# CrawlerProc_ver_02.net
KiCad netlist of a schematic drawn in EAGLE
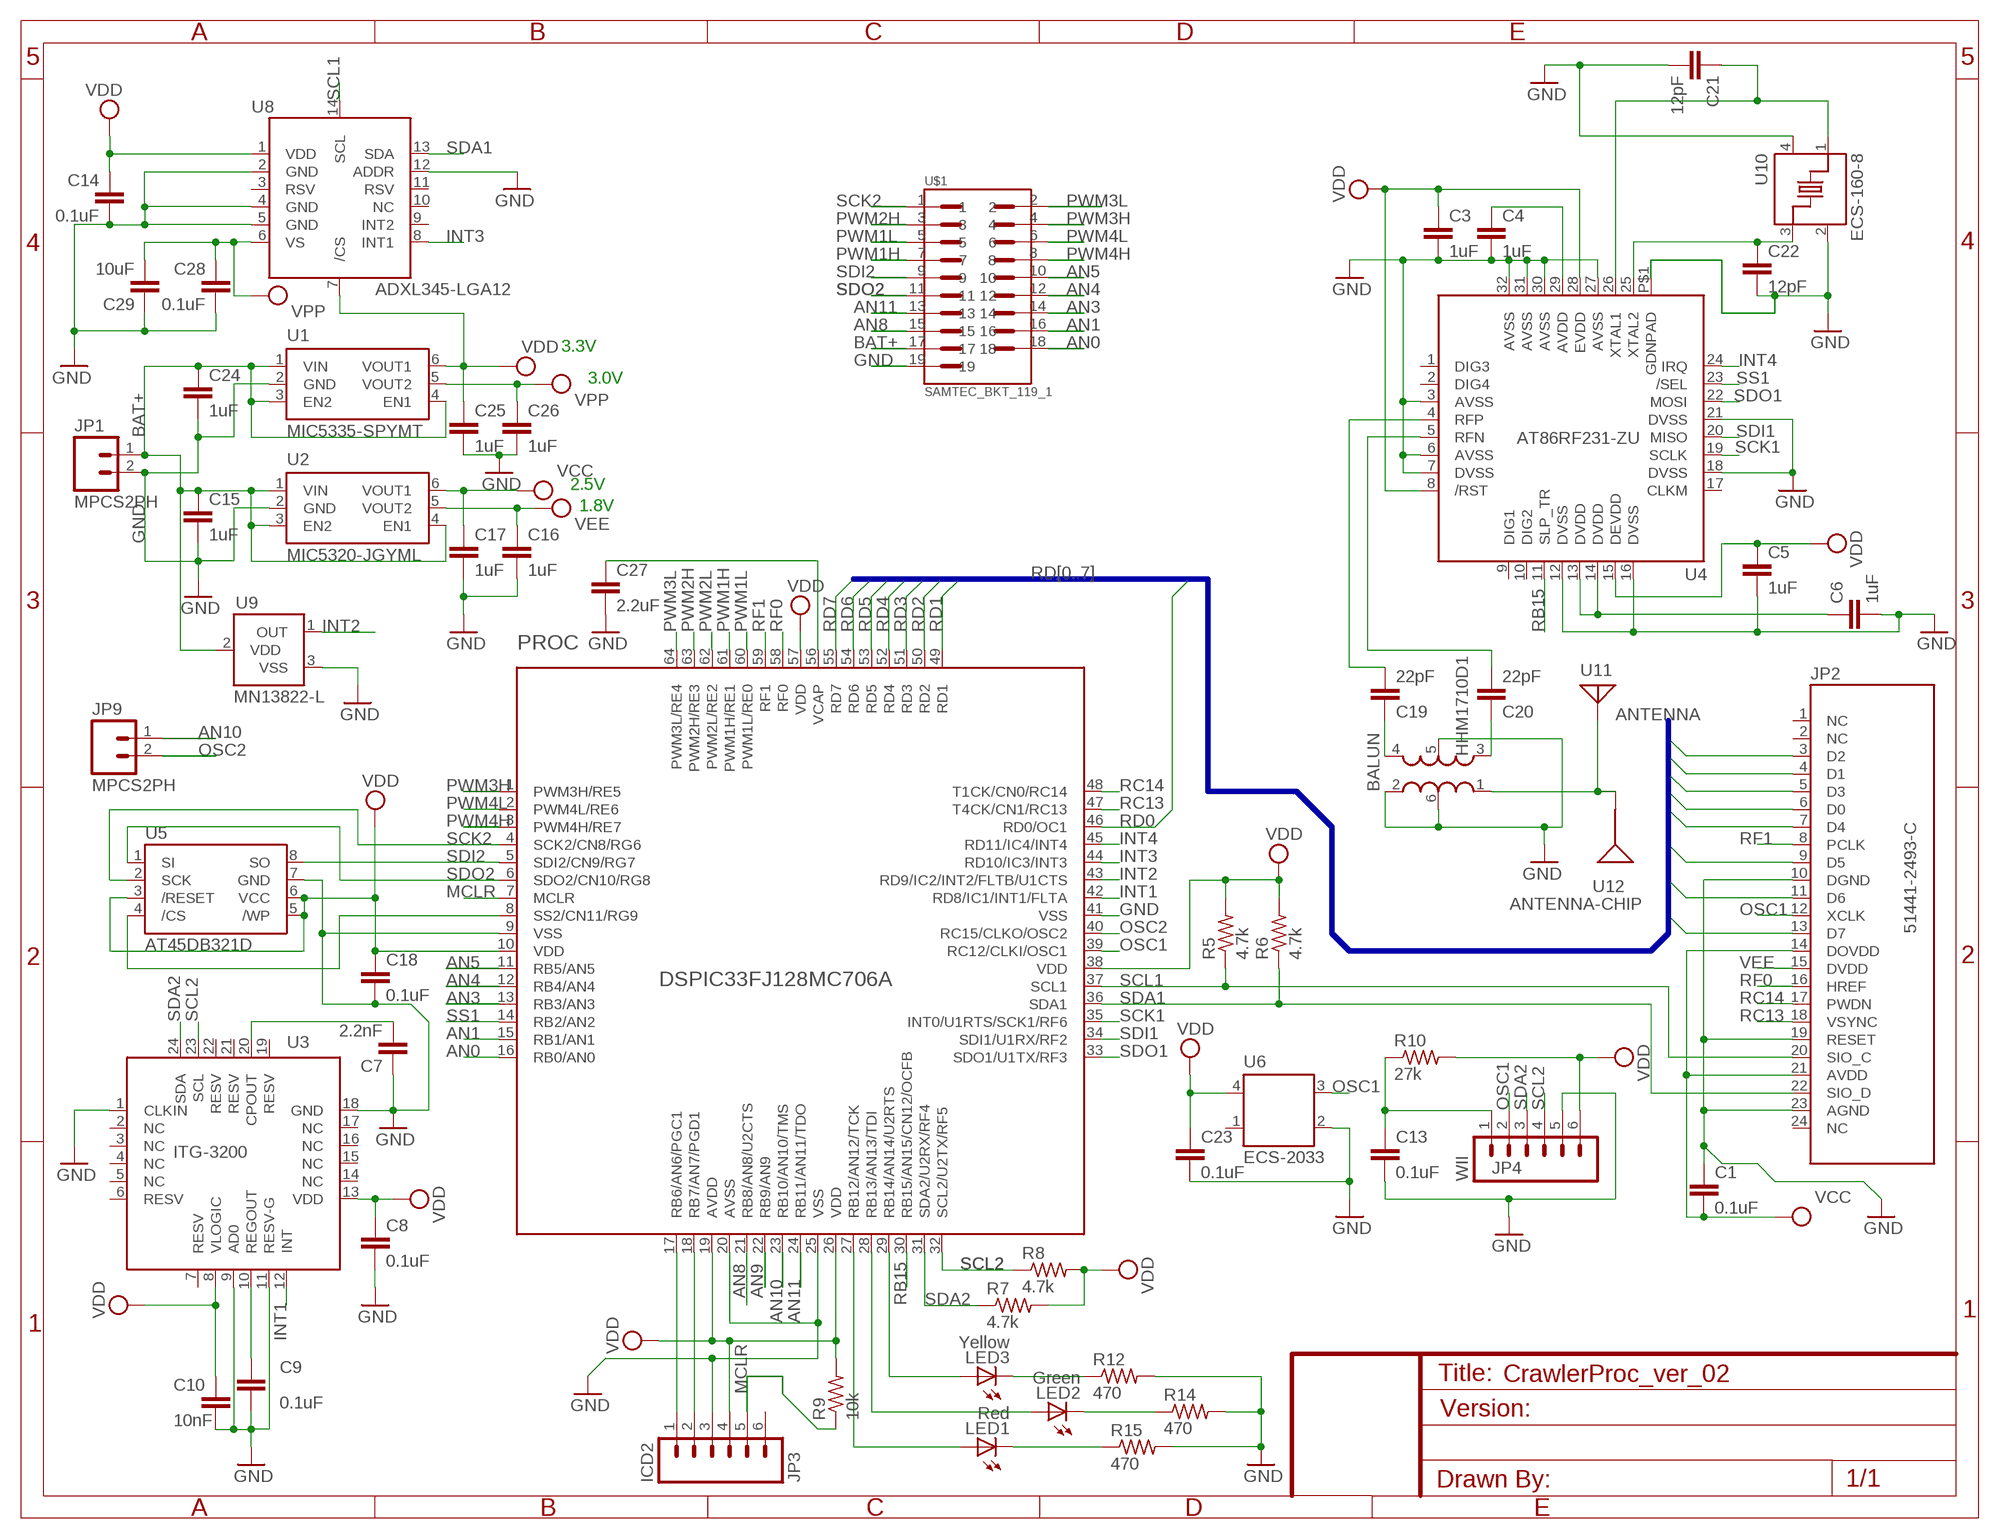
[diagram p0: schematic, sheet 1]

(export (version "E")
  (design (tool "Eeschema 10.0.6"))
  (components
    (comp (ref "BALUN")
      (value "HHM1710D1")
      (footprint "eagle-import:BALUN")
      (libsource (lib "eagle-import") (part "BALUNA"))
    )
    (comp (ref "C1")
      (value "0.1uF")
      (footprint "eagle-import:0402-CAP")
      (libsource (lib "eagle-import") (part "CAP0402-CAP"))
    )
    (comp (ref "C3")
      (value "1uF")
      (footprint "eagle-import:0402-CAP")
      (libsource (lib "eagle-import") (part "CAP0402-CAP"))
    )
    (comp (ref "C4")
      (value "1uF")
      (footprint "eagle-import:0402-CAP")
      (libsource (lib "eagle-import") (part "CAP0402-CAP"))
    )
    (comp (ref "C5")
      (value "1uF")
      (footprint "eagle-import:0402-CAP")
      (libsource (lib "eagle-import") (part "CAP0402-CAP"))
    )
    (comp (ref "C6")
      (value "1uF")
      (footprint "eagle-import:0402-CAP")
      (libsource (lib "eagle-import") (part "CAP0402-CAP"))
    )
    (comp (ref "C7")
      (value "2.2nF")
      (footprint "eagle-import:0402-CAP")
      (libsource (lib "eagle-import") (part "CAP0402-CAP"))
    )
    (comp (ref "C8")
      (value "0.1uF")
      (footprint "eagle-import:0402-CAP")
      (libsource (lib "eagle-import") (part "CAP0402-CAP"))
    )
    (comp (ref "C9")
      (value "0.1uF")
      (footprint "eagle-import:0402-CAP")
      (libsource (lib "eagle-import") (part "CAP0402-CAP"))
    )
    (comp (ref "C10")
      (value "10nF")
      (footprint "eagle-import:0402-CAP")
      (libsource (lib "eagle-import") (part "CAP0402-CAP"))
    )
    (comp (ref "C13")
      (value "0.1uF")
      (footprint "eagle-import:0402-CAP")
      (libsource (lib "eagle-import") (part "CAP0402-CAP"))
    )
    (comp (ref "C14")
      (value "0.1uF")
      (footprint "eagle-import:0402-CAP")
      (libsource (lib "eagle-import") (part "CAP0402-CAP"))
    )
    (comp (ref "C15")
      (value "1uF")
      (footprint "eagle-import:0402-CAP")
      (libsource (lib "eagle-import") (part "CAP0402-CAP"))
    )
    (comp (ref "C16")
      (value "1uF")
      (footprint "eagle-import:0402-CAP")
      (libsource (lib "eagle-import") (part "CAP0402-CAP"))
    )
    (comp (ref "C17")
      (value "1uF")
      (footprint "eagle-import:0402-CAP")
      (libsource (lib "eagle-import") (part "CAP0402-CAP"))
    )
    (comp (ref "C18")
      (value "0.1uF")
      (footprint "eagle-import:0402-CAP")
      (libsource (lib "eagle-import") (part "CAP0402-CAP"))
    )
    (comp (ref "C19")
      (value "22pF")
      (footprint "eagle-import:0402-CAP")
      (libsource (lib "eagle-import") (part "CAP0402-CAP"))
    )
    (comp (ref "C20")
      (value "22pF")
      (footprint "eagle-import:0402-CAP")
      (libsource (lib "eagle-import") (part "CAP0402-CAP"))
    )
    (comp (ref "C21")
      (value "12pF")
      (footprint "eagle-import:0402-CAP")
      (libsource (lib "eagle-import") (part "CAP0402-CAP"))
    )
    (comp (ref "C22")
      (value "12pF")
      (footprint "eagle-import:0402-CAP")
      (libsource (lib "eagle-import") (part "CAP0402-CAP"))
    )
    (comp (ref "C23")
      (value "0.1uF")
      (footprint "eagle-import:0402-CAP")
      (libsource (lib "eagle-import") (part "CAP0402-CAP"))
    )
    (comp (ref "C24")
      (value "1uF")
      (footprint "eagle-import:0402-CAP")
      (libsource (lib "eagle-import") (part "CAP0402-CAP"))
    )
    (comp (ref "C25")
      (value "1uF")
      (footprint "eagle-import:0402-CAP")
      (libsource (lib "eagle-import") (part "CAP0402-CAP"))
    )
    (comp (ref "C26")
      (value "1uF")
      (footprint "eagle-import:0402-CAP")
      (libsource (lib "eagle-import") (part "CAP0402-CAP"))
    )
    (comp (ref "C27")
      (value "2.2uF")
      (footprint "eagle-import:0402-CAP")
      (libsource (lib "eagle-import") (part "CAP0402-CAP"))
    )
    (comp (ref "C28")
      (value "0.1uF")
      (footprint "eagle-import:0402-CAP")
      (libsource (lib "eagle-import") (part "CAP0402-CAP"))
    )
    (comp (ref "C29")
      (value "10uF")
      (footprint "eagle-import:0603-CAP")
      (libsource (lib "eagle-import") (part "CAP0603-CAP"))
    )
    (comp (ref "JP1")
      (value "MPCS2PH")
      (footprint "eagle-import:MOLEX-PICO_CLASP_S2P")
      (libsource (lib "eagle-import") (part "MPCS2PH"))
    )
    (comp (ref "JP2")
      (value "51441-2493-C")
      (footprint "eagle-import:MOLEX-52740-2490")
      (libsource (lib "eagle-import") (part "OV7660FSL_CON-24"))
    )
    (comp (ref "JP3")
      (value "ICD2")
      (footprint "eagle-import:MOLEX-PICO_CLASP_S6P")
      (libsource (lib "eagle-import") (part "MPCS6PH"))
    )
    (comp (ref "JP4")
      (value "WII")
      (footprint "eagle-import:MOLEX-PICO_CLASP_S6P")
      (libsource (lib "eagle-import") (part "MPCS6PH"))
    )
    (comp (ref "JP9")
      (value "MPCS2PH")
      (footprint "eagle-import:MOLEX-PICO_CLASP_S2P")
      (libsource (lib "eagle-import") (part "MPCS2PH"))
    )
    (comp (ref "LED1")
      (value "Red")
      (footprint "eagle-import:CHIP-LED0603")
      (libsource (lib "eagle-import") (part "LEDCHIP-LED0603"))
    )
    (comp (ref "LED2")
      (value "Green")
      (footprint "eagle-import:CHIP-LED0603")
      (libsource (lib "eagle-import") (part "LEDCHIP-LED0603"))
    )
    (comp (ref "LED3")
      (value "Yellow")
      (footprint "eagle-import:CHIP-LED0603")
      (libsource (lib "eagle-import") (part "LEDCHIP-LED0603"))
    )
    (comp (ref "PROC")
      (value "DSPIC33FJ128MC706A")
      (footprint "eagle-import:TQFP64")
      (libsource (lib "eagle-import") (part "DSPIC33FJ128MC706-I/PT"))
    )
    (comp (ref "R5")
      (value "4.7k")
      (footprint "eagle-import:R0402")
      (libsource (lib "eagle-import") (part "R-US_R0402"))
    )
    (comp (ref "R6")
      (value "4.7k")
      (footprint "eagle-import:R0402")
      (libsource (lib "eagle-import") (part "R-US_R0402"))
    )
    (comp (ref "R7")
      (value "4.7k")
      (footprint "eagle-import:R0402")
      (libsource (lib "eagle-import") (part "R-US_R0402"))
    )
    (comp (ref "R8")
      (value "4.7k")
      (footprint "eagle-import:R0402")
      (libsource (lib "eagle-import") (part "R-US_R0402"))
    )
    (comp (ref "R9")
      (value "10k")
      (footprint "eagle-import:R0402")
      (libsource (lib "eagle-import") (part "R-US_R0402"))
    )
    (comp (ref "R10")
      (value "27k")
      (footprint "eagle-import:R0402")
      (libsource (lib "eagle-import") (part "R-US_R0402"))
    )
    (comp (ref "R12")
      (value "470")
      (footprint "eagle-import:R0402")
      (libsource (lib "eagle-import") (part "R-US_R0402"))
    )
    (comp (ref "R14")
      (value "470")
      (footprint "eagle-import:R0402")
      (libsource (lib "eagle-import") (part "R-US_R0402"))
    )
    (comp (ref "R15")
      (value "470")
      (footprint "eagle-import:R0402")
      (libsource (lib "eagle-import") (part "R-US_R0402"))
    )
    (comp (ref "U$1")
      (value "SAMTEC_BKT_119_1")
      (footprint "eagle-import:SAMTEC_19P_1MM_MICRO_CONN")
      (libsource (lib "eagle-import") (part "SAMTEC_BKT_119_1"))
    )
    (comp (ref "U1")
      (value "MIC5335-SPYMT")
      (footprint "eagle-import:MLF-6")
      (libsource (lib "eagle-import") (part "MIC5320-JGYML"))
    )
    (comp (ref "U2")
      (value "MIC5320-JGYML")
      (footprint "eagle-import:MLF-6")
      (libsource (lib "eagle-import") (part "MIC5320-JGYML"))
    )
    (comp (ref "U3")
      (value "ITG-3200")
      (footprint "eagle-import:QFN-24")
      (libsource (lib "eagle-import") (part "ITG-3200-00"))
    )
    (comp (ref "U4")
      (value "AT86RF231-ZU")
      (footprint "eagle-import:QFN-32")
      (libsource (lib "eagle-import") (part "AT86RF231-ZU"))
    )
    (comp (ref "U5")
      (value "AT45DB321D")
      (footprint "eagle-import:MLF(VDFN)-8")
      (libsource (lib "eagle-import") (part "AT45DB321D"))
    )
    (comp (ref "U6")
      (value "ECS-2033")
      (footprint "eagle-import:OSCILLATOR-SMD")
      (libsource (lib "eagle-import") (part "OSCILLATORS"))
    )
    (comp (ref "U8")
      (value "ADXL345-LGA12")
      (footprint "eagle-import:LGA14")
      (libsource (lib "eagle-import") (part "ADXL345"))
    )
    (comp (ref "U9")
      (value "MN13822-L")
      (footprint "eagle-import:SOT-23-3")
      (libsource (lib "eagle-import") (part "VOL_DETECTOR"))
    )
    (comp (ref "U10")
      (value "ECS-160-8")
      (footprint "eagle-import:CRYSTAL-SMD")
      (libsource (lib "eagle-import") (part "CRYSTALS"))
    )
    (comp (ref "U11")
      (value "ANTENNA")
      (footprint "eagle-import:ANTENNA_PAD")
      (libsource (lib "eagle-import") (part "ANTENNA"))
    )
    (comp (ref "U12")
      (value "ANTENNA-CHIP")
      (footprint "eagle-import:ANTENNA-CHIP")
      (libsource (lib "eagle-import") (part "ANTENNA-CHIP"))
    )
  )
  (nets
    (net (code "1") (name "/AN0") (class "Default")
      (node (ref "PROC") (pin "16") (pinfunction "RB0/AN0_16") (pintype "bidirectional"))
      (node (ref "U$1") (pin "18") (pinfunction "18_18") (pintype "passive"))
    )
    (net (code "2") (name "/AN1") (class "Default")
      (node (ref "PROC") (pin "15") (pinfunction "RB1/AN1_15") (pintype "bidirectional"))
      (node (ref "U$1") (pin "16") (pinfunction "16_16") (pintype "passive"))
    )
    (net (code "3") (name "/AN3") (class "Default")
      (node (ref "PROC") (pin "13") (pinfunction "RB3/AN3_13") (pintype "bidirectional"))
      (node (ref "U$1") (pin "14") (pinfunction "14_14") (pintype "passive"))
    )
    (net (code "4") (name "/AN4") (class "Default")
      (node (ref "PROC") (pin "12") (pinfunction "RB4/AN4_12") (pintype "bidirectional"))
      (node (ref "U$1") (pin "12") (pinfunction "12_12") (pintype "passive"))
    )
    (net (code "5") (name "/AN5") (class "Default")
      (node (ref "PROC") (pin "11") (pinfunction "RB5/AN5_11") (pintype "bidirectional"))
      (node (ref "U$1") (pin "10") (pinfunction "10_10") (pintype "passive"))
    )
    (net (code "6") (name "/AN8") (class "Default")
      (node (ref "PROC") (pin "21") (pinfunction "RB8/AN8/U2CTS_21") (pintype "bidirectional"))
      (node (ref "U$1") (pin "15") (pinfunction "15_15") (pintype "passive"))
    )
    (net (code "7") (name "/AN9") (class "Default")
      (node (ref "PROC") (pin "22") (pinfunction "RB9/AN9_22") (pintype "bidirectional"))
    )
    (net (code "8") (name "/AN10") (class "Default")
      (node (ref "JP9") (pin "1") (pinfunction "1_1") (pintype "passive"))
      (node (ref "PROC") (pin "23") (pinfunction "RB10/AN10/TMS_23") (pintype "bidirectional"))
    )
    (net (code "9") (name "/AN11") (class "Default")
      (node (ref "PROC") (pin "24") (pinfunction "RB11/AN11/TDO_24") (pintype "bidirectional"))
      (node (ref "U$1") (pin "13") (pinfunction "13_13") (pintype "passive"))
    )
    (net (code "10") (name "/BAT+") (class "Default")
      (node (ref "C15") (pin "1") (pinfunction "1_1") (pintype "passive"))
      (node (ref "C24") (pin "1") (pinfunction "1_1") (pintype "passive"))
      (node (ref "JP1") (pin "1") (pinfunction "1_1") (pintype "passive"))
      (node (ref "U$1") (pin "17") (pinfunction "17_17") (pintype "passive"))
      (node (ref "U1") (pin "1") (pinfunction "VIN_1") (pintype "bidirectional"))
      (node (ref "U1") (pin "3") (pinfunction "EN2_3") (pintype "bidirectional"))
      (node (ref "U1") (pin "4") (pinfunction "EN1_4") (pintype "bidirectional"))
      (node (ref "U2") (pin "1") (pinfunction "VIN_1") (pintype "bidirectional"))
      (node (ref "U2") (pin "3") (pinfunction "EN2_3") (pintype "bidirectional"))
      (node (ref "U2") (pin "4") (pinfunction "EN1_4") (pintype "bidirectional"))
      (node (ref "U9") (pin "2") (pinfunction "VDD_2") (pintype "bidirectional"))
    )
    (net (code "11") (name "/INT1") (class "Default")
      (node (ref "PROC") (pin "42") (pinfunction "RD8/IC1/INT1/FLTA_42") (pintype "bidirectional"))
      (node (ref "U3") (pin "12") (pinfunction "INT_12") (pintype "bidirectional"))
    )
    (net (code "12") (name "/INT2") (class "Default")
      (node (ref "PROC") (pin "43") (pinfunction "RD9/IC2/INT2/FLTB/U1CTS_43") (pintype "bidirectional"))
      (node (ref "U9") (pin "1") (pinfunction "OUT_1") (pintype "bidirectional"))
    )
    (net (code "13") (name "/INT3") (class "Default")
      (node (ref "PROC") (pin "44") (pinfunction "RD10/IC3/INT3_44") (pintype "bidirectional"))
      (node (ref "U8") (pin "8") (pinfunction "INT1_8") (pintype "bidirectional"))
    )
    (net (code "14") (name "/INT4") (class "Default")
      (node (ref "PROC") (pin "45") (pinfunction "RD11/IC4/INT4_45") (pintype "bidirectional"))
      (node (ref "U4") (pin "24") (pinfunction "IRQ_24") (pintype "bidirectional"))
    )
    (net (code "15") (name "/MCLR") (class "Default")
      (node (ref "JP3") (pin "5") (pinfunction "5_5") (pintype "passive"))
      (node (ref "PROC") (pin "7") (pinfunction "MCLR_7") (pintype "input"))
      (node (ref "R9") (pin "1") (pinfunction "1_1") (pintype "passive"))
    )
    (net (code "16") (name "/OSC1") (class "Default")
      (node (ref "JP2") (pin "12") (pinfunction "XCLK_12") (pintype "bidirectional"))
      (node (ref "JP4") (pin "2") (pinfunction "2_2") (pintype "passive"))
      (node (ref "PROC") (pin "39") (pinfunction "RC12/CLKI/OSC1_39") (pintype "bidirectional"))
      (node (ref "U6") (pin "3") (pinfunction "OUT_3") (pintype "bidirectional"))
    )
    (net (code "17") (name "/OSC2") (class "Default")
      (node (ref "JP9") (pin "2") (pinfunction "2_2") (pintype "passive"))
      (node (ref "PROC") (pin "40") (pinfunction "RC15/CLKO/OSC2_40") (pintype "bidirectional"))
    )
    (net (code "18") (name "/PWM1H") (class "Default")
      (node (ref "PROC") (pin "61") (pinfunction "PWM1H/RE1_61") (pintype "bidirectional"))
      (node (ref "U$1") (pin "7") (pinfunction "7_7") (pintype "passive"))
    )
    (net (code "19") (name "/PWM1L") (class "Default")
      (node (ref "PROC") (pin "60") (pinfunction "PWM1L/RE0_60") (pintype "bidirectional"))
      (node (ref "U$1") (pin "5") (pinfunction "5_5") (pintype "passive"))
    )
    (net (code "20") (name "/PWM2H") (class "Default")
      (node (ref "PROC") (pin "63") (pinfunction "PWM2H/RE3_63") (pintype "bidirectional"))
      (node (ref "U$1") (pin "3") (pinfunction "3_3") (pintype "passive"))
    )
    (net (code "21") (name "/PWM2L") (class "Default")
      (node (ref "PROC") (pin "62") (pinfunction "PWM2L/RE2_62") (pintype "bidirectional"))
    )
    (net (code "22") (name "/PWM3H") (class "Default")
      (node (ref "PROC") (pin "1") (pinfunction "PWM3H/RE5_1") (pintype "bidirectional"))
      (node (ref "U$1") (pin "4") (pinfunction "4_4") (pintype "passive"))
    )
    (net (code "23") (name "/PWM3L") (class "Default")
      (node (ref "PROC") (pin "64") (pinfunction "PWM3L/RE4_64") (pintype "bidirectional"))
      (node (ref "U$1") (pin "2") (pinfunction "2_2") (pintype "passive"))
    )
    (net (code "24") (name "/PWM4H") (class "Default")
      (node (ref "PROC") (pin "3") (pinfunction "PWM4H/RE7_3") (pintype "bidirectional"))
      (node (ref "U$1") (pin "8") (pinfunction "8_8") (pintype "passive"))
    )
    (net (code "25") (name "/PWM4L") (class "Default")
      (node (ref "PROC") (pin "2") (pinfunction "PWM4L/RE6_2") (pintype "bidirectional"))
      (node (ref "U$1") (pin "6") (pinfunction "6_6") (pintype "passive"))
    )
    (net (code "26") (name "/RB15") (class "Default")
      (node (ref "PROC") (pin "30") (pinfunction "RB15/AN15/CN12/OCFB_30") (pintype "bidirectional"))
      (node (ref "U4") (pin "11") (pinfunction "SLP_TR_11") (pintype "bidirectional"))
    )
    (net (code "27") (name "/RC13") (class "Default")
      (node (ref "JP2") (pin "18") (pinfunction "VSYNC_18") (pintype "bidirectional"))
      (node (ref "PROC") (pin "47") (pinfunction "T4CK/CN1/RC13_47") (pintype "bidirectional"))
    )
    (net (code "28") (name "/RC14") (class "Default")
      (node (ref "JP2") (pin "17") (pinfunction "PWDN_17") (pintype "bidirectional"))
      (node (ref "PROC") (pin "48") (pinfunction "T1CK/CN0/RC14_48") (pintype "bidirectional"))
    )
    (net (code "29") (name "/RD0") (class "Default")
      (node (ref "JP2") (pin "6") (pinfunction "D0_6") (pintype "bidirectional"))
      (node (ref "PROC") (pin "46") (pinfunction "RD0/OC1_46") (pintype "bidirectional"))
    )
    (net (code "30") (name "/RD1") (class "Default")
      (node (ref "JP2") (pin "4") (pinfunction "D1_4") (pintype "bidirectional"))
      (node (ref "PROC") (pin "49") (pinfunction "RD1_49") (pintype "bidirectional"))
    )
    (net (code "31") (name "/RD2") (class "Default")
      (node (ref "JP2") (pin "3") (pinfunction "D2_3") (pintype "bidirectional"))
      (node (ref "PROC") (pin "50") (pinfunction "RD2_50") (pintype "bidirectional"))
    )
    (net (code "32") (name "/RD3") (class "Default")
      (node (ref "JP2") (pin "5") (pinfunction "D3_5") (pintype "bidirectional"))
      (node (ref "PROC") (pin "51") (pinfunction "RD3_51") (pintype "bidirectional"))
    )
    (net (code "33") (name "/RD4") (class "Default")
      (node (ref "JP2") (pin "7") (pinfunction "D4_7") (pintype "bidirectional"))
      (node (ref "PROC") (pin "52") (pinfunction "RD4_52") (pintype "bidirectional"))
    )
    (net (code "34") (name "/RD5") (class "Default")
      (node (ref "JP2") (pin "9") (pinfunction "D5_9") (pintype "bidirectional"))
      (node (ref "PROC") (pin "53") (pinfunction "RD5_53") (pintype "bidirectional"))
    )
    (net (code "35") (name "/RD6") (class "Default")
      (node (ref "JP2") (pin "11") (pinfunction "D6_11") (pintype "bidirectional"))
      (node (ref "PROC") (pin "54") (pinfunction "RD6_54") (pintype "bidirectional"))
    )
    (net (code "36") (name "/RD7") (class "Default")
      (node (ref "JP2") (pin "13") (pinfunction "D7_13") (pintype "bidirectional"))
      (node (ref "PROC") (pin "55") (pinfunction "RD7_55") (pintype "bidirectional"))
    )
    (net (code "38") (name "/RF0") (class "Default")
      (node (ref "JP2") (pin "16") (pinfunction "HREF_16") (pintype "bidirectional"))
      (node (ref "PROC") (pin "58") (pinfunction "RF0_58") (pintype "bidirectional"))
    )
    (net (code "39") (name "/RF1") (class "Default")
      (node (ref "JP2") (pin "8") (pinfunction "PCLK_8") (pintype "bidirectional"))
      (node (ref "PROC") (pin "59") (pinfunction "RF1_59") (pintype "bidirectional"))
    )
    (net (code "40") (name "/SCK1") (class "Default")
      (node (ref "PROC") (pin "35") (pinfunction "INT0/U1RTS/SCK1/RF6_35") (pintype "bidirectional"))
      (node (ref "U4") (pin "19") (pinfunction "SCLK_19") (pintype "bidirectional"))
    )
    (net (code "41") (name "/SCK2") (class "Default")
      (node (ref "PROC") (pin "4") (pinfunction "SCK2/CN8/RG6_4") (pintype "bidirectional"))
      (node (ref "U$1") (pin "1") (pinfunction "1_1") (pintype "passive"))
      (node (ref "U5") (pin "2") (pinfunction "SCK_2") (pintype "bidirectional"))
    )
    (net (code "42") (name "/SCL1") (class "Default")
      (node (ref "JP2") (pin "20") (pinfunction "SIO_C_20") (pintype "bidirectional"))
      (node (ref "PROC") (pin "37") (pinfunction "SCL1_37") (pintype "bidirectional"))
      (node (ref "R5") (pin "1") (pinfunction "1_1") (pintype "passive"))
      (node (ref "U8") (pin "14") (pinfunction "SCL_14") (pintype "bidirectional"))
    )
    (net (code "43") (name "/SCL2") (class "Default")
      (node (ref "JP4") (pin "4") (pinfunction "4_4") (pintype "passive"))
      (node (ref "PROC") (pin "32") (pinfunction "SCL2/U2TX/RF5_32") (pintype "bidirectional"))
      (node (ref "R8") (pin "1") (pinfunction "1_1") (pintype "passive"))
      (node (ref "U3") (pin "23") (pinfunction "SCL_23") (pintype "bidirectional"))
    )
    (net (code "44") (name "/SDA1") (class "Default")
      (node (ref "JP2") (pin "22") (pinfunction "SIO_D_22") (pintype "bidirectional"))
      (node (ref "PROC") (pin "36") (pinfunction "SDA1_36") (pintype "bidirectional"))
      (node (ref "R6") (pin "1") (pinfunction "1_1") (pintype "passive"))
      (node (ref "U8") (pin "13") (pinfunction "SDA_13") (pintype "bidirectional"))
    )
    (net (code "45") (name "/SDA2") (class "Default")
      (node (ref "JP4") (pin "3") (pinfunction "3_3") (pintype "passive"))
      (node (ref "PROC") (pin "31") (pinfunction "SDA2/U2RX/RF4_31") (pintype "bidirectional"))
      (node (ref "R7") (pin "1") (pinfunction "1_1") (pintype "passive"))
      (node (ref "U3") (pin "24") (pinfunction "SDA_24") (pintype "bidirectional"))
    )
    (net (code "46") (name "/SDI1") (class "Default")
      (node (ref "PROC") (pin "34") (pinfunction "SDI1/U1RX/RF2_34") (pintype "bidirectional"))
      (node (ref "U4") (pin "20") (pinfunction "MISO_20") (pintype "bidirectional"))
    )
    (net (code "47") (name "/SDI2") (class "Default")
      (node (ref "PROC") (pin "5") (pinfunction "SDI2/CN9/RG7_5") (pintype "bidirectional"))
      (node (ref "U$1") (pin "9") (pinfunction "9_9") (pintype "passive"))
      (node (ref "U5") (pin "8") (pinfunction "SO_8") (pintype "bidirectional"))
    )
    (net (code "48") (name "/SDO1") (class "Default")
      (node (ref "PROC") (pin "33") (pinfunction "SDO1/U1TX/RF3_33") (pintype "bidirectional"))
      (node (ref "U4") (pin "22") (pinfunction "MOSI_22") (pintype "bidirectional"))
    )
    (net (code "49") (name "/SDO2") (class "Default")
      (node (ref "PROC") (pin "6") (pinfunction "SDO2/CN10/RG8_6") (pintype "bidirectional"))
      (node (ref "U$1") (pin "11") (pinfunction "11_11") (pintype "passive"))
      (node (ref "U5") (pin "1") (pinfunction "SI_1") (pintype "bidirectional"))
    )
    (net (code "50") (name "/SS1") (class "Default")
      (node (ref "PROC") (pin "14") (pinfunction "RB2/AN2_14") (pintype "bidirectional"))
      (node (ref "U4") (pin "23") (pinfunction "/SEL_23") (pintype "bidirectional"))
    )
    (net (code "51") (name "GND") (class "Default")
      (node (ref "BALUN") (pin "2") (pinfunction "RFGND_2") (pintype "bidirectional"))
      (node (ref "BALUN") (pin "5") (pinfunction "GND_5") (pintype "bidirectional"))
      (node (ref "BALUN") (pin "6") (pinfunction "NC_6") (pintype "bidirectional"))
      (node (ref "C1") (pin "1") (pinfunction "1_1") (pintype "passive"))
      (node (ref "C10") (pin "2") (pinfunction "2_2") (pintype "passive"))
      (node (ref "C13") (pin "2") (pinfunction "2_2") (pintype "passive"))
      (node (ref "C14") (pin "2") (pinfunction "2_2") (pintype "passive"))
      (node (ref "C15") (pin "2") (pinfunction "2_2") (pintype "passive"))
      (node (ref "C16") (pin "2") (pinfunction "2_2") (pintype "passive"))
      (node (ref "C17") (pin "2") (pinfunction "2_2") (pintype "passive"))
      (node (ref "C18") (pin "2") (pinfunction "2_2") (pintype "passive"))
      (node (ref "C21") (pin "2") (pinfunction "2_2") (pintype "passive"))
      (node (ref "C22") (pin "2") (pinfunction "2_2") (pintype "passive"))
      (node (ref "C23") (pin "2") (pinfunction "2_2") (pintype "passive"))
      (node (ref "C24") (pin "2") (pinfunction "2_2") (pintype "passive"))
      (node (ref "C25") (pin "2") (pinfunction "2_2") (pintype "passive"))
      (node (ref "C26") (pin "2") (pinfunction "2_2") (pintype "passive"))
      (node (ref "C27") (pin "2") (pinfunction "2_2") (pintype "passive"))
      (node (ref "C28") (pin "2") (pinfunction "2_2") (pintype "passive"))
      (node (ref "C29") (pin "1") (pinfunction "1_1") (pintype "passive"))
      (node (ref "C3") (pin "2") (pinfunction "2_2") (pintype "passive"))
      (node (ref "C4") (pin "2") (pinfunction "2_2") (pintype "passive"))
      (node (ref "C5") (pin "2") (pinfunction "2_2") (pintype "passive"))
      (node (ref "C6") (pin "2") (pinfunction "2_2") (pintype "passive"))
      (node (ref "C7") (pin "1") (pinfunction "1_1") (pintype "passive"))
      (node (ref "C8") (pin "2") (pinfunction "2_2") (pintype "passive"))
      (node (ref "C9") (pin "2") (pinfunction "2_2") (pintype "passive"))
      (node (ref "JP1") (pin "2") (pinfunction "2_2") (pintype "passive"))
      (node (ref "JP2") (pin "10") (pinfunction "DGND_10") (pintype "bidirectional"))
      (node (ref "JP2") (pin "19") (pinfunction "RESET_19") (pintype "bidirectional"))
      (node (ref "JP2") (pin "23") (pinfunction "AGND_23") (pintype "bidirectional"))
      (node (ref "JP3") (pin "3") (pinfunction "3_3") (pintype "passive"))
      (node (ref "JP4") (pin "5") (pinfunction "5_5") (pintype "passive"))
      (node (ref "PROC") (pin "20") (pinfunction "AVSS_20") (pintype "power_in"))
      (node (ref "PROC") (pin "25") (pinfunction "VSS_25") (pintype "power_in"))
      (node (ref "PROC") (pin "41") (pinfunction "VSS_41") (pintype "power_in"))
      (node (ref "PROC") (pin "9") (pinfunction "VSS_9") (pintype "power_in"))
      (node (ref "R12") (pin "2") (pinfunction "2_2") (pintype "passive"))
      (node (ref "R14") (pin "2") (pinfunction "2_2") (pintype "passive"))
      (node (ref "R15") (pin "2") (pinfunction "2_2") (pintype "passive"))
      (node (ref "U$1") (pin "19") (pinfunction "19_19") (pintype "passive"))
      (node (ref "U1") (pin "2") (pinfunction "GND_2") (pintype "bidirectional"))
      (node (ref "U10") (pin "2") (pinfunction "GND_2") (pintype "bidirectional"))
      (node (ref "U10") (pin "4") (pinfunction "GND_4") (pintype "bidirectional"))
      (node (ref "U2") (pin "2") (pinfunction "GND_2") (pintype "bidirectional"))
      (node (ref "U3") (pin "1") (pinfunction "CLKIN_1") (pintype "bidirectional"))
      (node (ref "U3") (pin "11") (pinfunction "RESV-G_11") (pintype "bidirectional"))
      (node (ref "U3") (pin "18") (pinfunction "GND_18") (pintype "bidirectional"))
      (node (ref "U3") (pin "9") (pinfunction "AD0_9") (pintype "bidirectional"))
      (node (ref "U4") (pin "12") (pinfunction "DVSS_12") (pintype "bidirectional"))
      (node (ref "U4") (pin "16") (pinfunction "DVSS_16") (pintype "bidirectional"))
      (node (ref "U4") (pin "18") (pinfunction "DVSS_18") (pintype "bidirectional"))
      (node (ref "U4") (pin "21") (pinfunction "DVSS_21") (pintype "bidirectional"))
      (node (ref "U4") (pin "27") (pinfunction "AVSS_27") (pintype "bidirectional"))
      (node (ref "U4") (pin "3") (pinfunction "AVSS_3") (pintype "bidirectional"))
      (node (ref "U4") (pin "30") (pinfunction "AVSS_30") (pintype "bidirectional"))
      (node (ref "U4") (pin "31") (pinfunction "AVSS_31") (pintype "bidirectional"))
      (node (ref "U4") (pin "32") (pinfunction "AVSS_32") (pintype "bidirectional"))
      (node (ref "U4") (pin "6") (pinfunction "AVSS_6") (pintype "bidirectional"))
      (node (ref "U4") (pin "7") (pinfunction "DVSS_7") (pintype "bidirectional"))
      (node (ref "U4") (pin "P$1") (pinfunction "GDNPAD_P$1") (pintype "bidirectional"))
      (node (ref "U5") (pin "7") (pinfunction "GND_7") (pintype "bidirectional"))
      (node (ref "U6") (pin "2") (pinfunction "GND_2") (pintype "bidirectional"))
      (node (ref "U8") (pin "12") (pinfunction "ADDR_12") (pintype "bidirectional"))
      (node (ref "U8") (pin "2") (pinfunction "GND_2") (pintype "bidirectional"))
      (node (ref "U8") (pin "4") (pinfunction "GND_4") (pintype "bidirectional"))
      (node (ref "U8") (pin "5") (pinfunction "GND_5") (pintype "bidirectional"))
      (node (ref "U9") (pin "3") (pinfunction "VSS_3") (pintype "bidirectional"))
    )
    (net (code "52") (name "Net-(BALUN-BAL3)") (class "Default")
      (node (ref "BALUN") (pin "3") (pinfunction "BAL3_3") (pintype "bidirectional"))
      (node (ref "C20") (pin "1") (pinfunction "1_1") (pintype "passive"))
    )
    (net (code "53") (name "Net-(BALUN-BAL4)") (class "Default")
      (node (ref "BALUN") (pin "4") (pinfunction "BAL4_4") (pintype "bidirectional"))
      (node (ref "C19") (pin "1") (pinfunction "1_1") (pintype "passive"))
    )
    (net (code "54") (name "Net-(BALUN-UNBAL)") (class "Default")
      (node (ref "BALUN") (pin "1") (pinfunction "UNBAL_1") (pintype "bidirectional"))
      (node (ref "U11") (pin "P$1") (pinfunction "1_P$1") (pintype "output"))
      (node (ref "U12") (pin "SIG") (pinfunction "SIGNAL_SIG") (pintype "bidirectional"))
    )
    (net (code "55") (name "Net-(C6-Pad1)") (class "Default")
      (node (ref "C6") (pin "1") (pinfunction "1_1") (pintype "passive"))
      (node (ref "U4") (pin "13") (pinfunction "DVDD_13") (pintype "bidirectional"))
      (node (ref "U4") (pin "14") (pinfunction "DVDD_14") (pintype "bidirectional"))
    )
    (net (code "56") (name "Net-(C13-Pad1)") (class "Default")
      (node (ref "C13") (pin "1") (pinfunction "1_1") (pintype "passive"))
      (node (ref "JP4") (pin "1") (pinfunction "1_1") (pintype "passive"))
      (node (ref "R10") (pin "1") (pinfunction "1_1") (pintype "passive"))
    )
    (net (code "57") (name "Net-(LED1-PadC)") (class "Default")
      (node (ref "LED1") (pin "C") (pinfunction "C_C") (pintype "passive"))
      (node (ref "R15") (pin "1") (pinfunction "1_1") (pintype "passive"))
    )
    (net (code "58") (name "Net-(LED2-PadC)") (class "Default")
      (node (ref "LED2") (pin "C") (pinfunction "C_C") (pintype "passive"))
      (node (ref "R14") (pin "1") (pinfunction "1_1") (pintype "passive"))
    )
    (net (code "59") (name "Net-(LED3-PadC)") (class "Default")
      (node (ref "LED3") (pin "C") (pinfunction "C_C") (pintype "passive"))
      (node (ref "R12") (pin "1") (pinfunction "1_1") (pintype "passive"))
    )
    (net (code "60") (name "Net-(PROC-RB6{slash}AN6{slash}PGC1)") (class "Default")
      (node (ref "JP3") (pin "1") (pinfunction "1_1") (pintype "passive"))
      (node (ref "PROC") (pin "17") (pinfunction "RB6/AN6/PGC1_17") (pintype "bidirectional"))
    )
    (net (code "61") (name "Net-(PROC-RB7{slash}AN7{slash}PGD1)") (class "Default")
      (node (ref "JP3") (pin "2") (pinfunction "2_2") (pintype "passive"))
      (node (ref "PROC") (pin "18") (pinfunction "RB7/AN7/PGD1_18") (pintype "bidirectional"))
    )
    (net (code "62") (name "Net-(PROC-RB12{slash}AN12{slash}TCK)") (class "Default")
      (node (ref "LED1") (pin "A") (pinfunction "A_A") (pintype "passive"))
      (node (ref "PROC") (pin "27") (pinfunction "RB12/AN12/TCK_27") (pintype "bidirectional"))
    )
    (net (code "63") (name "Net-(PROC-RB13{slash}AN13{slash}TDI)") (class "Default")
      (node (ref "LED2") (pin "A") (pinfunction "A_A") (pintype "passive"))
      (node (ref "PROC") (pin "28") (pinfunction "RB13/AN13/TDI_28") (pintype "bidirectional"))
    )
    (net (code "64") (name "Net-(PROC-RB14{slash}AN14{slash}U2RTS)") (class "Default")
      (node (ref "LED3") (pin "A") (pinfunction "A_A") (pintype "passive"))
      (node (ref "PROC") (pin "29") (pinfunction "RB14/AN14/U2RTS_29") (pintype "bidirectional"))
    )
    (net (code "65") (name "Net-(PROC-SS2{slash}CN11{slash}RG9)") (class "Default")
      (node (ref "PROC") (pin "8") (pinfunction "SS2/CN11/RG9_8") (pintype "bidirectional"))
      (node (ref "U5") (pin "4") (pinfunction "/CS_4") (pintype "bidirectional"))
    )
    (net (code "66") (name "Net-(PROC-VCAP)") (class "Default")
      (node (ref "C27") (pin "1") (pinfunction "1_1") (pintype "passive"))
      (node (ref "PROC") (pin "56") (pinfunction "VCAP_56") (pintype "power_in"))
    )
    (net (code "67") (name "Net-(U3-CPOUT)") (class "Default")
      (node (ref "C7") (pin "2") (pinfunction "2_2") (pintype "passive"))
      (node (ref "U3") (pin "20") (pinfunction "CPOUT_20") (pintype "bidirectional"))
    )
    (net (code "68") (name "Net-(U3-REGOUT)") (class "Default")
      (node (ref "C9") (pin "1") (pinfunction "1_1") (pintype "passive"))
      (node (ref "U3") (pin "10") (pinfunction "REGOUT_10") (pintype "bidirectional"))
    )
    (net (code "69") (name "Net-(U4-AVDD)") (class "Default")
      (node (ref "C4") (pin "1") (pinfunction "1_1") (pintype "passive"))
      (node (ref "U4") (pin "29") (pinfunction "AVDD_29") (pintype "bidirectional"))
    )
    (net (code "70") (name "Net-(U4-RFN)") (class "Default")
      (node (ref "C20") (pin "2") (pinfunction "2_2") (pintype "passive"))
      (node (ref "U4") (pin "5") (pinfunction "RFN_5") (pintype "bidirectional"))
    )
    (net (code "71") (name "Net-(U4-RFP)") (class "Default")
      (node (ref "C19") (pin "2") (pinfunction "2_2") (pintype "passive"))
      (node (ref "U4") (pin "4") (pinfunction "RFP_4") (pintype "bidirectional"))
    )
    (net (code "72") (name "Net-(U4-XTAL1)") (class "Default")
      (node (ref "C21") (pin "1") (pinfunction "1_1") (pintype "passive"))
      (node (ref "U10") (pin "1") (pinfunction "IN/OUT_1") (pintype "bidirectional"))
      (node (ref "U4") (pin "26") (pinfunction "XTAL1_26") (pintype "bidirectional"))
    )
    (net (code "73") (name "Net-(U4-XTAL2)") (class "Default")
      (node (ref "C22") (pin "1") (pinfunction "1_1") (pintype "passive"))
      (node (ref "U10") (pin "3") (pinfunction "IN/OUT_3") (pintype "bidirectional"))
      (node (ref "U4") (pin "25") (pinfunction "XTAL2_25") (pintype "bidirectional"))
    )
    (net (code "74") (name "VCC") (class "Default")
      (node (ref "C1") (pin "2") (pinfunction "2_2") (pintype "passive"))
      (node (ref "C17") (pin "1") (pinfunction "1_1") (pintype "passive"))
      (node (ref "JP2") (pin "14") (pinfunction "DOVDD_14") (pintype "bidirectional"))
      (node (ref "JP2") (pin "21") (pinfunction "AVDD_21") (pintype "bidirectional"))
      (node (ref "U2") (pin "6") (pinfunction "VOUT1_6") (pintype "bidirectional"))
    )
    (net (code "75") (name "VDD") (class "Default")
      (node (ref "C10") (pin "1") (pinfunction "1_1") (pintype "passive"))
      (node (ref "C14") (pin "1") (pinfunction "1_1") (pintype "passive"))
      (node (ref "C18") (pin "1") (pinfunction "1_1") (pintype "passive"))
      (node (ref "C23") (pin "1") (pinfunction "1_1") (pintype "passive"))
      (node (ref "C25") (pin "1") (pinfunction "1_1") (pintype "passive"))
      (node (ref "C3") (pin "1") (pinfunction "1_1") (pintype "passive"))
      (node (ref "C5") (pin "1") (pinfunction "1_1") (pintype "passive"))
      (node (ref "C8") (pin "1") (pinfunction "1_1") (pintype "passive"))
      (node (ref "JP3") (pin "4") (pinfunction "4_4") (pintype "passive"))
      (node (ref "JP4") (pin "6") (pinfunction "6_6") (pintype "passive"))
      (node (ref "PROC") (pin "10") (pinfunction "VDD_10") (pintype "power_in"))
      (node (ref "PROC") (pin "19") (pinfunction "AVDD_19") (pintype "power_in"))
      (node (ref "PROC") (pin "26") (pinfunction "VDD_26") (pintype "power_in"))
      (node (ref "PROC") (pin "38") (pinfunction "VDD_38") (pintype "power_in"))
      (node (ref "PROC") (pin "57") (pinfunction "VDD_57") (pintype "power_in"))
      (node (ref "R10") (pin "2") (pinfunction "2_2") (pintype "passive"))
      (node (ref "R5") (pin "2") (pinfunction "2_2") (pintype "passive"))
      (node (ref "R6") (pin "2") (pinfunction "2_2") (pintype "passive"))
      (node (ref "R7") (pin "2") (pinfunction "2_2") (pintype "passive"))
      (node (ref "R8") (pin "2") (pinfunction "2_2") (pintype "passive"))
      (node (ref "R9") (pin "2") (pinfunction "2_2") (pintype "passive"))
      (node (ref "U1") (pin "6") (pinfunction "VOUT1_6") (pintype "bidirectional"))
      (node (ref "U3") (pin "13") (pinfunction "VDD_13") (pintype "bidirectional"))
      (node (ref "U3") (pin "8") (pinfunction "VLOGIC_8") (pintype "bidirectional"))
      (node (ref "U4") (pin "15") (pinfunction "DEVDD_15") (pintype "bidirectional"))
      (node (ref "U4") (pin "28") (pinfunction "EVDD_28") (pintype "bidirectional"))
      (node (ref "U4") (pin "8") (pinfunction "/RST_8") (pintype "bidirectional"))
      (node (ref "U5") (pin "3") (pinfunction "/RESET_3") (pintype "bidirectional"))
      (node (ref "U5") (pin "5") (pinfunction "/WP_5") (pintype "bidirectional"))
      (node (ref "U5") (pin "6") (pinfunction "VCC_6") (pintype "bidirectional"))
      (node (ref "U6") (pin "4") (pinfunction "VDD_4") (pintype "bidirectional"))
      (node (ref "U8") (pin "1") (pinfunction "VDD_1") (pintype "bidirectional"))
      (node (ref "U8") (pin "7") (pinfunction "/CS_7") (pintype "bidirectional"))
    )
    (net (code "76") (name "VEE") (class "Default")
      (node (ref "C16") (pin "1") (pinfunction "1_1") (pintype "passive"))
      (node (ref "JP2") (pin "15") (pinfunction "DVDD_15") (pintype "bidirectional"))
      (node (ref "U2") (pin "5") (pinfunction "VOUT2_5") (pintype "bidirectional"))
    )
    (net (code "77") (name "VPP") (class "Default")
      (node (ref "C26") (pin "1") (pinfunction "1_1") (pintype "passive"))
      (node (ref "C28") (pin "1") (pinfunction "1_1") (pintype "passive"))
      (node (ref "C29") (pin "2") (pinfunction "2_2") (pintype "passive"))
      (node (ref "U1") (pin "5") (pinfunction "VOUT2_5") (pintype "bidirectional"))
      (node (ref "U8") (pin "6") (pinfunction "VS_6") (pintype "bidirectional"))
    )
    (net (code "78") (name "unconnected-(JP2-NC-Pad1)") (class "Default")
      (node (ref "JP2") (pin "1") (pinfunction "NC_1") (pintype "bidirectional"))
    )
    (net (code "79") (name "unconnected-(JP2-NC-Pad2)") (class "Default")
      (node (ref "JP2") (pin "2") (pinfunction "NC_2") (pintype "bidirectional"))
    )
    (net (code "80") (name "unconnected-(JP2-NC-Pad24)") (class "Default")
      (node (ref "JP2") (pin "24") (pinfunction "NC_24") (pintype "bidirectional"))
    )
    (net (code "81") (name "unconnected-(JP3-Pad6)") (class "Default")
      (node (ref "JP3") (pin "6") (pinfunction "6_6") (pintype "passive"))
    )
    (net (code "82") (name "unconnected-(U3-NC-Pad2)") (class "Default")
      (node (ref "U3") (pin "2") (pinfunction "NC_2") (pintype "bidirectional"))
    )
    (net (code "83") (name "unconnected-(U3-NC-Pad3)") (class "Default")
      (node (ref "U3") (pin "3") (pinfunction "NC_3") (pintype "bidirectional"))
    )
    (net (code "84") (name "unconnected-(U3-NC-Pad4)") (class "Default")
      (node (ref "U3") (pin "4") (pinfunction "NC_4") (pintype "bidirectional"))
    )
    (net (code "85") (name "unconnected-(U3-NC-Pad5)") (class "Default")
      (node (ref "U3") (pin "5") (pinfunction "NC_5") (pintype "bidirectional"))
    )
    (net (code "86") (name "unconnected-(U3-NC-Pad14)") (class "Default")
      (node (ref "U3") (pin "14") (pinfunction "NC_14") (pintype "bidirectional"))
    )
    (net (code "87") (name "unconnected-(U3-NC-Pad15)") (class "Default")
      (node (ref "U3") (pin "15") (pinfunction "NC_15") (pintype "bidirectional"))
    )
    (net (code "88") (name "unconnected-(U3-NC-Pad16)") (class "Default")
      (node (ref "U3") (pin "16") (pinfunction "NC_16") (pintype "bidirectional"))
    )
    (net (code "89") (name "unconnected-(U3-NC-Pad17)") (class "Default")
      (node (ref "U3") (pin "17") (pinfunction "NC_17") (pintype "bidirectional"))
    )
    (net (code "90") (name "unconnected-(U3-RESV-Pad6)") (class "Default")
      (node (ref "U3") (pin "6") (pinfunction "RESV_6") (pintype "bidirectional"))
    )
    (net (code "91") (name "unconnected-(U3-RESV-Pad7)") (class "Default")
      (node (ref "U3") (pin "7") (pinfunction "RESV_7") (pintype "bidirectional"))
    )
    (net (code "92") (name "unconnected-(U3-RESV-Pad19)") (class "Default")
      (node (ref "U3") (pin "19") (pinfunction "RESV_19") (pintype "bidirectional"))
    )
    (net (code "93") (name "unconnected-(U3-RESV-Pad21)") (class "Default")
      (node (ref "U3") (pin "21") (pinfunction "RESV_21") (pintype "bidirectional"))
    )
    (net (code "94") (name "unconnected-(U3-RESV-Pad22)") (class "Default")
      (node (ref "U3") (pin "22") (pinfunction "RESV_22") (pintype "bidirectional"))
    )
    (net (code "95") (name "unconnected-(U4-CLKM-Pad17)") (class "Default")
      (node (ref "U4") (pin "17") (pinfunction "CLKM_17") (pintype "bidirectional"))
    )
    (net (code "96") (name "unconnected-(U4-DIG1-Pad9)") (class "Default")
      (node (ref "U4") (pin "9") (pinfunction "DIG1_9") (pintype "bidirectional"))
    )
    (net (code "97") (name "unconnected-(U4-DIG2-Pad10)") (class "Default")
      (node (ref "U4") (pin "10") (pinfunction "DIG2_10") (pintype "bidirectional"))
    )
    (net (code "98") (name "unconnected-(U4-DIG3-Pad1)") (class "Default")
      (node (ref "U4") (pin "1") (pinfunction "DIG3_1") (pintype "bidirectional"))
    )
    (net (code "99") (name "unconnected-(U4-DIG4-Pad2)") (class "Default")
      (node (ref "U4") (pin "2") (pinfunction "DIG4_2") (pintype "bidirectional"))
    )
    (net (code "100") (name "unconnected-(U6-NC-Pad1)") (class "Default")
      (node (ref "U6") (pin "1") (pinfunction "NC_1") (pintype "bidirectional"))
    )
    (net (code "101") (name "unconnected-(U8-INT2-Pad9)") (class "Default")
      (node (ref "U8") (pin "9") (pinfunction "INT2_9") (pintype "bidirectional"))
    )
    (net (code "102") (name "unconnected-(U8-NC-Pad10)") (class "Default")
      (node (ref "U8") (pin "10") (pinfunction "NC_10") (pintype "bidirectional"))
    )
    (net (code "103") (name "unconnected-(U8-RSV-Pad3)") (class "Default")
      (node (ref "U8") (pin "3") (pinfunction "RSV_3") (pintype "bidirectional"))
    )
    (net (code "104") (name "unconnected-(U8-RSV-Pad11)") (class "Default")
      (node (ref "U8") (pin "11") (pinfunction "RSV_11") (pintype "bidirectional"))
    )
  )
)
